# CPU_EBI1_FPGA_Memory.net
KiCad netlist of a schematic drawn in Altium Designer
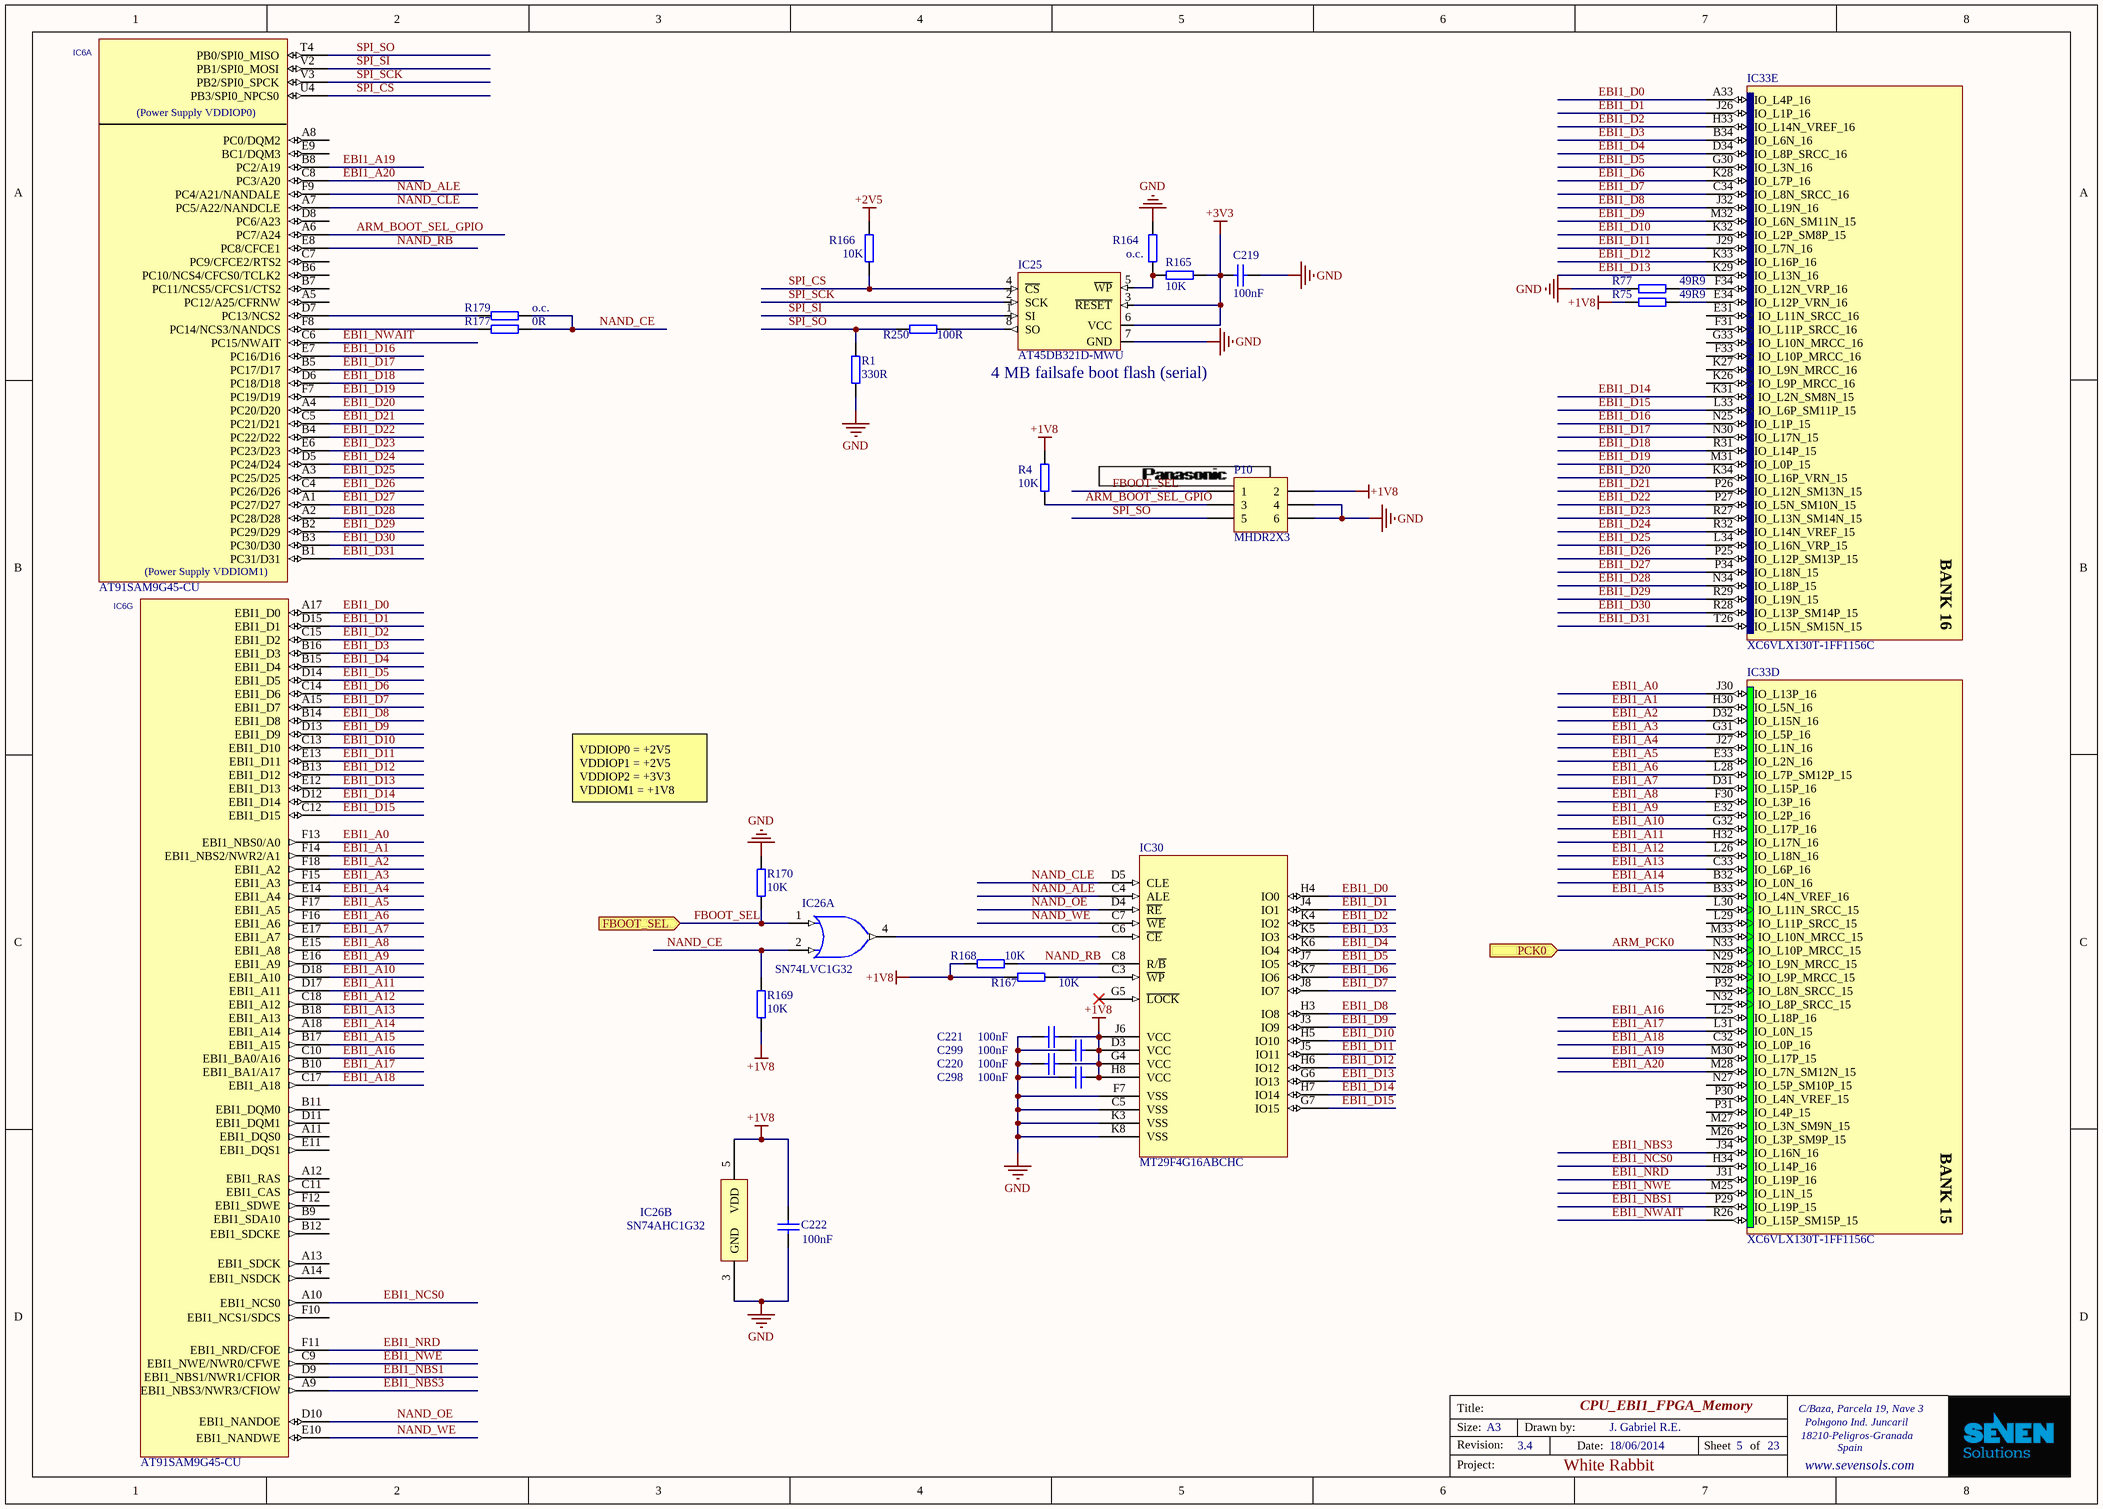
[diagram p0: CPU_EBI1_FPGA_Memory.SchDoc]

(export (version "E")
  (design (tool "Eeschema 10.0.6"))
  (components
    (comp (ref "C219")
      (value "100nF")
      (footprint "CC1005-0402")
      (description "Capacitor")
      (fields
        (field (name "TOLERANCE") "±10%")
        (field (name "VOLTAGE") "16V")
        (field (name "PUBLISHER") "Altium Limited")
      )
      (libsource (lib "wr_switch") (part "Cap"))
    )
    (comp (ref "C220")
      (value "100nF")
      (footprint "CC1005-0402")
      (description "Capacitor")
      (fields
        (field (name "TOLERANCE") "±10%")
        (field (name "VOLTAGE") "16V")
        (field (name "PUBLISHER") "Altium Limited")
      )
      (libsource (lib "wr_switch") (part "Cap"))
    )
    (comp (ref "C221")
      (value "100nF")
      (footprint "CC1005-0402")
      (description "Capacitor")
      (fields
        (field (name "TOLERANCE") "±10%")
        (field (name "VOLTAGE") "16V")
        (field (name "PUBLISHER") "Altium Limited")
      )
      (libsource (lib "wr_switch") (part "Cap"))
    )
    (comp (ref "C222")
      (value "100nF")
      (footprint "CC1005-0402")
      (description "Capacitor")
      (fields
        (field (name "TOLERANCE") "±10%")
        (field (name "VOLTAGE") "16V")
        (field (name "PUBLISHER") "Altium Limited")
      )
      (libsource (lib "wr_switch") (part "Cap"))
    )
    (comp (ref "C298")
      (value "100nF")
      (footprint "CC1005-0402")
      (description "Capacitor")
      (fields
        (field (name "TOLERANCE") "±10%")
        (field (name "VOLTAGE") "16V")
        (field (name "PUBLISHER") "Altium Limited")
      )
      (libsource (lib "wr_switch") (part "Cap"))
    )
    (comp (ref "C299")
      (value "100nF")
      (footprint "CC1005-0402")
      (description "Capacitor")
      (fields
        (field (name "TOLERANCE") "±10%")
        (field (name "VOLTAGE") "16V")
        (field (name "PUBLISHER") "Altium Limited")
      )
      (libsource (lib "wr_switch") (part "Cap"))
    )
    (comp (ref "IC6")
      (value "AT91SAM9G45-CU")
      (footprint "TFBGA324")
      (description "Atmel 400MHz ARM926 MCU")
      (libsource (lib "wr_switch") (part "AT91SAM9G45-CU"))
    )
    (comp (ref "IC25")
      (value "AT45DB321D-MWU")
      (footprint "7S_WR:8MW_8CN3_Merge")
      (description "64-megabit 2.7V, Dual-Interface DataFlash")
      (libsource (lib "wr_switch") (part "AT45DB642D"))
    )
    (comp (ref "IC26")
      (value "SN74LVC1G32")
      (footprint "SOT23-5AL")
      (description "TI single OR gate")
      (libsource (lib "wr_switch") (part "SN74AHC1G32"))
    )
    (comp (ref "IC30")
      (value "MT29F4G16ABCHC")
      (footprint "7S_WR:VFBGA63")
      (description "NAND Flash 256Mx16, 1.8V Asynch/Page")
      (libsource (lib "wr_switch") (part "MT29F4G16ABCHC"))
    )
    (comp (ref "IC33")
      (value "XC6VLX130T-1FF1156C")
      (footprint "FF1156")
      (fields (field (name "PUBLISHER") "Altium Limited"))
      (libsource (lib "Xilinx Virtex-6") (part "XC6VLX130T-1FF1156C"))
    )
    (comp (ref "P10")
      (value "MHDR2X3")
      (footprint "7S_WR:MHDR2X3_1.27mm")
      (description "SMD Header, 3-Pin, Dual row, 2.54mm pitch")
      (libsource (lib "Miscellaneous Connectors") (part "MHDR2X3"))
    )
    (comp (ref "R1")
      (value "330R")
      (footprint "0402")
      (description "SMD Resistor")
      (fields (field (name "TOLERANCE") "±1%"))
      (libsource (lib "wr_switch") (part "RES_SMD"))
    )
    (comp (ref "R4")
      (value "10K")
      (footprint "0402")
      (description "SMD Resistor")
      (fields (field (name "TOLERANCE") "±1%"))
      (libsource (lib "wr_switch") (part "RES_SMD"))
    )
    (comp (ref "R75")
      (value "49R9")
      (footprint "0402")
      (description "SMD Resistor")
      (fields (field (name "TOLERANCE") "±1%"))
      (libsource (lib "wr_switch") (part "RES_SMD"))
    )
    (comp (ref "R77")
      (value "49R9")
      (footprint "0402")
      (description "SMD Resistor")
      (fields (field (name "TOLERANCE") "±1%"))
      (libsource (lib "wr_switch") (part "RES_SMD"))
    )
    (comp (ref "R164")
      (value "o.c.")
      (footprint "0402")
      (description "SMD Resistor")
      (libsource (lib "wr_switch") (part "RES_SMD"))
    )
    (comp (ref "R165")
      (value "10K")
      (footprint "0402")
      (description "SMD Resistor")
      (fields (field (name "TOLERANCE") "±1%"))
      (libsource (lib "wr_switch") (part "RES_SMD"))
    )
    (comp (ref "R166")
      (value "10K")
      (footprint "0402")
      (description "SMD Resistor")
      (fields (field (name "TOLERANCE") "±1%"))
      (libsource (lib "wr_switch") (part "RES_SMD"))
    )
    (comp (ref "R167")
      (value "10K")
      (footprint "0402")
      (description "SMD Resistor")
      (fields (field (name "TOLERANCE") "±1%"))
      (libsource (lib "wr_switch") (part "RES_SMD"))
    )
    (comp (ref "R168")
      (value "10K")
      (footprint "0402")
      (description "SMD Resistor")
      (fields (field (name "TOLERANCE") "±1%"))
      (libsource (lib "wr_switch") (part "RES_SMD"))
    )
    (comp (ref "R169")
      (value "10K")
      (footprint "0402")
      (description "SMD Resistor")
      (fields (field (name "TOLERANCE") "±1%"))
      (libsource (lib "wr_switch") (part "RES_SMD"))
    )
    (comp (ref "R170")
      (value "10K")
      (footprint "0402")
      (description "SMD Resistor")
      (fields (field (name "TOLERANCE") "±1%"))
      (libsource (lib "wr_switch") (part "RES_SMD"))
    )
    (comp (ref "R177")
      (value "0R")
      (footprint "0603")
      (description "SMD Resistor")
      (libsource (lib "wr_switch") (part "RES_SMD"))
    )
    (comp (ref "R179")
      (value "o.c.")
      (footprint "0402")
      (description "SMD Resistor")
      (libsource (lib "wr_switch") (part "RES_SMD"))
    )
    (comp (ref "R250")
      (value "100R")
      (footprint "0402")
      (description "SMD Resistor")
      (fields (field (name "TOLERANCE") "±1%"))
      (libsource (lib "wr_switch") (part "RES_SMD"))
    )
  )
  (nets
    (net (code "1") (name "+1V8") (class "Default")
      (node (ref "C220") (pin "1") (pinfunction "1_1") (pintype "passive"))
      (node (ref "C221") (pin "1") (pinfunction "1_1") (pintype "passive"))
      (node (ref "C222") (pin "2") (pinfunction "2_2") (pintype "passive"))
      (node (ref "C298") (pin "1") (pinfunction "1_1") (pintype "passive"))
      (node (ref "C299") (pin "1") (pinfunction "1_1") (pintype "passive"))
      (node (ref "IC26") (pin "5") (pinfunction "VDD_5") (pintype "passive"))
      (node (ref "IC30") (pin "D3") (pinfunction "VCC_D3") (pintype "power_in"))
      (node (ref "IC30") (pin "G4") (pinfunction "VCC_G4") (pintype "power_in"))
      (node (ref "IC30") (pin "H8") (pinfunction "VCC_H8") (pintype "power_in"))
      (node (ref "IC30") (pin "J6") (pinfunction "VCC_J6") (pintype "power_in"))
      (node (ref "P10") (pin "2") (pinfunction "2_2") (pintype "passive"))
      (node (ref "R167") (pin "2") (pinfunction "2_2") (pintype "passive"))
      (node (ref "R168") (pin "2") (pinfunction "2_2") (pintype "passive"))
      (node (ref "R169") (pin "2") (pinfunction "2_2") (pintype "passive"))
      (node (ref "R4") (pin "2") (pinfunction "2_2") (pintype "passive"))
      (node (ref "R75") (pin "2") (pinfunction "2_2") (pintype "passive"))
    )
    (net (code "2") (name "+2V5") (class "Default")
      (node (ref "R166") (pin "2") (pinfunction "2_2") (pintype "passive"))
    )
    (net (code "3") (name "+3V3") (class "Default")
      (node (ref "C219") (pin "1") (pinfunction "1_1") (pintype "passive"))
      (node (ref "IC25") (pin "3") (pinfunction "~{RESET}_3") (pintype "input"))
      (node (ref "IC25") (pin "6") (pinfunction "VCC_6") (pintype "power_in"))
      (node (ref "R165") (pin "2") (pinfunction "2_2") (pintype "passive"))
    )
    (net (code "4") (name "/ARM_BOOT_SEL_GPIO") (class "Default")
      (node (ref "IC6") (pin "A6") (pinfunction "PC7/A24_A6") (pintype "bidirectional"))
      (node (ref "P10") (pin "3") (pinfunction "3_3") (pintype "passive"))
      (node (ref "R4") (pin "1") (pinfunction "1_1") (pintype "passive"))
    )
    (net (code "5") (name "/ARM_PCK0") (class "Default")
      (node (ref "IC33") (pin "N33") (pinfunction "IO_L10P_MRCC_15_N33") (pintype "bidirectional"))
    )
    (net (code "6") (name "/EBI1_A0") (class "Default")
      (node (ref "IC33") (pin "J30") (pinfunction "IO_L13P_16_J30") (pintype "bidirectional"))
      (node (ref "IC6") (pin "F13") (pinfunction "EBI1_NBS0/A0_F13") (pintype "output"))
    )
    (net (code "7") (name "/EBI1_A1") (class "Default")
      (node (ref "IC33") (pin "H30") (pinfunction "IO_L5N_16_H30") (pintype "bidirectional"))
      (node (ref "IC6") (pin "F14") (pinfunction "EBI1_NBS2/NWR2/A1_F14") (pintype "output"))
    )
    (net (code "8") (name "/EBI1_A2") (class "Default")
      (node (ref "IC33") (pin "D32") (pinfunction "IO_L15N_16_D32") (pintype "bidirectional"))
      (node (ref "IC6") (pin "F18") (pinfunction "EBI1_A2_F18") (pintype "output"))
    )
    (net (code "9") (name "/EBI1_A3") (class "Default")
      (node (ref "IC33") (pin "G31") (pinfunction "IO_L5P_16_G31") (pintype "bidirectional"))
      (node (ref "IC6") (pin "F15") (pinfunction "EBI1_A3_F15") (pintype "output"))
    )
    (net (code "10") (name "/EBI1_A4") (class "Default")
      (node (ref "IC33") (pin "J27") (pinfunction "IO_L1N_16_J27") (pintype "bidirectional"))
      (node (ref "IC6") (pin "E14") (pinfunction "EBI1_A4_E14") (pintype "output"))
    )
    (net (code "11") (name "/EBI1_A5") (class "Default")
      (node (ref "IC33") (pin "E33") (pinfunction "IO_L2N_16_E33") (pintype "bidirectional"))
      (node (ref "IC6") (pin "F17") (pinfunction "EBI1_A5_F17") (pintype "output"))
    )
    (net (code "12") (name "/EBI1_A6") (class "Default")
      (node (ref "IC33") (pin "L28") (pinfunction "IO_L7P_SM12P_15_L28") (pintype "bidirectional"))
      (node (ref "IC6") (pin "F16") (pinfunction "EBI1_A6_F16") (pintype "output"))
    )
    (net (code "13") (name "/EBI1_A7") (class "Default")
      (node (ref "IC33") (pin "D31") (pinfunction "IO_L15P_16_D31") (pintype "bidirectional"))
      (node (ref "IC6") (pin "E17") (pinfunction "EBI1_A7_E17") (pintype "output"))
    )
    (net (code "14") (name "/EBI1_A8") (class "Default")
      (node (ref "IC33") (pin "F30") (pinfunction "IO_L3P_16_F30") (pintype "bidirectional"))
      (node (ref "IC6") (pin "E15") (pinfunction "EBI1_A8_E15") (pintype "output"))
    )
    (net (code "15") (name "/EBI1_A9") (class "Default")
      (node (ref "IC33") (pin "E32") (pinfunction "IO_L2P_16_E32") (pintype "bidirectional"))
      (node (ref "IC6") (pin "E16") (pinfunction "EBI1_A9_E16") (pintype "output"))
    )
    (net (code "16") (name "/EBI1_A10") (class "Default")
      (node (ref "IC33") (pin "G32") (pinfunction "IO_L17P_16_G32") (pintype "bidirectional"))
      (node (ref "IC6") (pin "D18") (pinfunction "EBI1_A10_D18") (pintype "output"))
    )
    (net (code "17") (name "/EBI1_A11") (class "Default")
      (node (ref "IC33") (pin "H32") (pinfunction "IO_L17N_16_H32") (pintype "bidirectional"))
      (node (ref "IC6") (pin "D17") (pinfunction "EBI1_A11_D17") (pintype "output"))
    )
    (net (code "18") (name "/EBI1_A12") (class "Default")
      (node (ref "IC33") (pin "L26") (pinfunction "IO_L18N_16_L26") (pintype "bidirectional"))
      (node (ref "IC6") (pin "C18") (pinfunction "EBI1_A12_C18") (pintype "output"))
    )
    (net (code "19") (name "/EBI1_A13") (class "Default")
      (node (ref "IC33") (pin "C33") (pinfunction "IO_L6P_16_C33") (pintype "bidirectional"))
      (node (ref "IC6") (pin "B18") (pinfunction "EBI1_A13_B18") (pintype "output"))
    )
    (net (code "20") (name "/EBI1_A14") (class "Default")
      (node (ref "IC33") (pin "B32") (pinfunction "IO_L0N_16_B32") (pintype "bidirectional"))
      (node (ref "IC6") (pin "A18") (pinfunction "EBI1_A14_A18") (pintype "output"))
    )
    (net (code "21") (name "/EBI1_A15") (class "Default")
      (node (ref "IC33") (pin "B33") (pinfunction "IO_L4N_VREF_16_B33") (pintype "bidirectional"))
      (node (ref "IC6") (pin "B17") (pinfunction "EBI1_A15_B17") (pintype "output"))
    )
    (net (code "22") (name "/EBI1_A16") (class "Default")
      (node (ref "IC33") (pin "L25") (pinfunction "IO_L18P_16_L25") (pintype "bidirectional"))
      (node (ref "IC6") (pin "C10") (pinfunction "EBI1_BA0/A16_C10") (pintype "output"))
    )
    (net (code "23") (name "/EBI1_A17") (class "Default")
      (node (ref "IC33") (pin "L31") (pinfunction "IO_L0N_15_L31") (pintype "bidirectional"))
      (node (ref "IC6") (pin "B10") (pinfunction "EBI1_BA1/A17_B10") (pintype "output"))
    )
    (net (code "24") (name "/EBI1_A18") (class "Default")
      (node (ref "IC33") (pin "C32") (pinfunction "IO_L0P_16_C32") (pintype "bidirectional"))
      (node (ref "IC6") (pin "C17") (pinfunction "EBI1_A18_C17") (pintype "output"))
    )
    (net (code "25") (name "/EBI1_A19") (class "Default")
      (node (ref "IC33") (pin "M30") (pinfunction "IO_L17P_15_M30") (pintype "bidirectional"))
      (node (ref "IC6") (pin "B8") (pinfunction "PC2/A19_B8") (pintype "bidirectional"))
    )
    (net (code "26") (name "/EBI1_A20") (class "Default")
      (node (ref "IC33") (pin "M28") (pinfunction "IO_L7N_SM12N_15_M28") (pintype "bidirectional"))
      (node (ref "IC6") (pin "C8") (pinfunction "PC3/A20_C8") (pintype "bidirectional"))
    )
    (net (code "27") (name "/EBI1_D0") (class "Default")
      (node (ref "IC30") (pin "H4") (pinfunction "IO0_H4") (pintype "bidirectional"))
      (node (ref "IC33") (pin "A33") (pinfunction "IO_L4P_16_A33") (pintype "bidirectional"))
      (node (ref "IC6") (pin "A17") (pinfunction "EBI1_D0_A17") (pintype "bidirectional"))
    )
    (net (code "28") (name "/EBI1_D1") (class "Default")
      (node (ref "IC30") (pin "J4") (pinfunction "IO1_J4") (pintype "bidirectional"))
      (node (ref "IC33") (pin "J26") (pinfunction "IO_L1P_16_J26") (pintype "bidirectional"))
      (node (ref "IC6") (pin "D15") (pinfunction "EBI1_D1_D15") (pintype "bidirectional"))
    )
    (net (code "29") (name "/EBI1_D2") (class "Default")
      (node (ref "IC30") (pin "K4") (pinfunction "IO2_K4") (pintype "bidirectional"))
      (node (ref "IC33") (pin "H33") (pinfunction "IO_L14N_VREF_16_H33") (pintype "bidirectional"))
      (node (ref "IC6") (pin "C15") (pinfunction "EBI1_D2_C15") (pintype "bidirectional"))
    )
    (net (code "30") (name "/EBI1_D3") (class "Default")
      (node (ref "IC30") (pin "K5") (pinfunction "IO3_K5") (pintype "bidirectional"))
      (node (ref "IC33") (pin "B34") (pinfunction "IO_L6N_16_B34") (pintype "bidirectional"))
      (node (ref "IC6") (pin "B16") (pinfunction "EBI1_D3_B16") (pintype "bidirectional"))
    )
    (net (code "31") (name "/EBI1_D4") (class "Default")
      (node (ref "IC30") (pin "K6") (pinfunction "IO4_K6") (pintype "bidirectional"))
      (node (ref "IC33") (pin "D34") (pinfunction "IO_L8P_SRCC_16_D34") (pintype "bidirectional"))
      (node (ref "IC6") (pin "B15") (pinfunction "EBI1_D4_B15") (pintype "bidirectional"))
    )
    (net (code "32") (name "/EBI1_D5") (class "Default")
      (node (ref "IC30") (pin "J7") (pinfunction "IO5_J7") (pintype "bidirectional"))
      (node (ref "IC33") (pin "G30") (pinfunction "IO_L3N_16_G30") (pintype "bidirectional"))
      (node (ref "IC6") (pin "D14") (pinfunction "EBI1_D5_D14") (pintype "bidirectional"))
    )
    (net (code "33") (name "/EBI1_D6") (class "Default")
      (node (ref "IC30") (pin "K7") (pinfunction "IO6_K7") (pintype "bidirectional"))
      (node (ref "IC33") (pin "K28") (pinfunction "IO_L7P_16_K28") (pintype "bidirectional"))
      (node (ref "IC6") (pin "C14") (pinfunction "EBI1_D6_C14") (pintype "bidirectional"))
    )
    (net (code "34") (name "/EBI1_D7") (class "Default")
      (node (ref "IC30") (pin "J8") (pinfunction "IO7_J8") (pintype "bidirectional"))
      (node (ref "IC33") (pin "C34") (pinfunction "IO_L8N_SRCC_16_C34") (pintype "bidirectional"))
      (node (ref "IC6") (pin "A15") (pinfunction "EBI1_D7_A15") (pintype "bidirectional"))
    )
    (net (code "35") (name "/EBI1_D8") (class "Default")
      (node (ref "IC30") (pin "H3") (pinfunction "IO8_H3") (pintype "bidirectional"))
      (node (ref "IC33") (pin "J32") (pinfunction "IO_L19N_16_J32") (pintype "bidirectional"))
      (node (ref "IC6") (pin "B14") (pinfunction "EBI1_D8_B14") (pintype "bidirectional"))
    )
    (net (code "36") (name "/EBI1_D9") (class "Default")
      (node (ref "IC30") (pin "J3") (pinfunction "IO9_J3") (pintype "bidirectional"))
      (node (ref "IC33") (pin "M32") (pinfunction "IO_L6N_SM11N_15_M32") (pintype "bidirectional"))
      (node (ref "IC6") (pin "D13") (pinfunction "EBI1_D9_D13") (pintype "bidirectional"))
    )
    (net (code "37") (name "/EBI1_D10") (class "Default")
      (node (ref "IC30") (pin "H5") (pinfunction "IO10_H5") (pintype "bidirectional"))
      (node (ref "IC33") (pin "K32") (pinfunction "IO_L2P_SM8P_15_K32") (pintype "bidirectional"))
      (node (ref "IC6") (pin "C13") (pinfunction "EBI1_D10_C13") (pintype "bidirectional"))
    )
    (net (code "38") (name "/EBI1_D11") (class "Default")
      (node (ref "IC30") (pin "J5") (pinfunction "IO11_J5") (pintype "bidirectional"))
      (node (ref "IC33") (pin "J29") (pinfunction "IO_L7N_16_J29") (pintype "bidirectional"))
      (node (ref "IC6") (pin "E13") (pinfunction "EBI1_D11_E13") (pintype "bidirectional"))
    )
    (net (code "39") (name "/EBI1_D12") (class "Default")
      (node (ref "IC30") (pin "H6") (pinfunction "IO12_H6") (pintype "bidirectional"))
      (node (ref "IC33") (pin "K33") (pinfunction "IO_L16P_16_K33") (pintype "bidirectional"))
      (node (ref "IC6") (pin "B13") (pinfunction "EBI1_D12_B13") (pintype "bidirectional"))
    )
    (net (code "40") (name "/EBI1_D13") (class "Default")
      (node (ref "IC30") (pin "G6") (pinfunction "IO13_G6") (pintype "bidirectional"))
      (node (ref "IC33") (pin "K29") (pinfunction "IO_L13N_16_K29") (pintype "bidirectional"))
      (node (ref "IC6") (pin "E12") (pinfunction "EBI1_D13_E12") (pintype "bidirectional"))
    )
    (net (code "41") (name "/EBI1_D14") (class "Default")
      (node (ref "IC30") (pin "H7") (pinfunction "IO14_H7") (pintype "bidirectional"))
      (node (ref "IC33") (pin "K31") (pinfunction "IO_L2N_SM8N_15_K31") (pintype "bidirectional"))
      (node (ref "IC6") (pin "D12") (pinfunction "EBI1_D14_D12") (pintype "bidirectional"))
    )
    (net (code "42") (name "/EBI1_D15") (class "Default")
      (node (ref "IC30") (pin "G7") (pinfunction "IO15_G7") (pintype "bidirectional"))
      (node (ref "IC33") (pin "L33") (pinfunction "IO_L6P_SM11P_15_L33") (pintype "bidirectional"))
      (node (ref "IC6") (pin "C12") (pinfunction "EBI1_D15_C12") (pintype "bidirectional"))
    )
    (net (code "43") (name "/EBI1_D16") (class "Default")
      (node (ref "IC33") (pin "N25") (pinfunction "IO_L1P_15_N25") (pintype "bidirectional"))
      (node (ref "IC6") (pin "E7") (pinfunction "PC16/D16_E7") (pintype "bidirectional"))
    )
    (net (code "44") (name "/EBI1_D17") (class "Default")
      (node (ref "IC33") (pin "N30") (pinfunction "IO_L17N_15_N30") (pintype "bidirectional"))
      (node (ref "IC6") (pin "B5") (pinfunction "PC17/D17_B5") (pintype "bidirectional"))
    )
    (net (code "45") (name "/EBI1_D18") (class "Default")
      (node (ref "IC33") (pin "R31") (pinfunction "IO_L14P_15_R31") (pintype "bidirectional"))
      (node (ref "IC6") (pin "D6") (pinfunction "PC18/D18_D6") (pintype "bidirectional"))
    )
    (net (code "46") (name "/EBI1_D19") (class "Default")
      (node (ref "IC33") (pin "M31") (pinfunction "IO_L0P_15_M31") (pintype "bidirectional"))
      (node (ref "IC6") (pin "F7") (pinfunction "PC19/D19_F7") (pintype "bidirectional"))
    )
    (net (code "47") (name "/EBI1_D20") (class "Default")
      (node (ref "IC33") (pin "K34") (pinfunction "IO_L16P_VRN_15_K34") (pintype "bidirectional"))
      (node (ref "IC6") (pin "A4") (pinfunction "PC20/D20_A4") (pintype "bidirectional"))
    )
    (net (code "48") (name "/EBI1_D21") (class "Default")
      (node (ref "IC33") (pin "P26") (pinfunction "IO_L12N_SM13N_15_P26") (pintype "bidirectional"))
      (node (ref "IC6") (pin "C5") (pinfunction "PC21/D21_C5") (pintype "bidirectional"))
    )
    (net (code "49") (name "/EBI1_D22") (class "Default")
      (node (ref "IC33") (pin "P27") (pinfunction "IO_L5N_SM10N_15_P27") (pintype "bidirectional"))
      (node (ref "IC6") (pin "B4") (pinfunction "PC22/D22_B4") (pintype "bidirectional"))
    )
    (net (code "50") (name "/EBI1_D23") (class "Default")
      (node (ref "IC33") (pin "R27") (pinfunction "IO_L13N_SM14N_15_R27") (pintype "bidirectional"))
      (node (ref "IC6") (pin "E6") (pinfunction "PC23/D23_E6") (pintype "bidirectional"))
    )
    (net (code "51") (name "/EBI1_D24") (class "Default")
      (node (ref "IC33") (pin "R32") (pinfunction "IO_L14N_VREF_15_R32") (pintype "bidirectional"))
      (node (ref "IC6") (pin "D5") (pinfunction "PC24/D24_D5") (pintype "bidirectional"))
    )
    (net (code "52") (name "/EBI1_D25") (class "Default")
      (node (ref "IC33") (pin "L34") (pinfunction "IO_L16N_VRP_15_L34") (pintype "bidirectional"))
      (node (ref "IC6") (pin "A3") (pinfunction "PC25/D25_A3") (pintype "bidirectional"))
    )
    (net (code "53") (name "/EBI1_D26") (class "Default")
      (node (ref "IC33") (pin "P25") (pinfunction "IO_L12P_SM13P_15_P25") (pintype "bidirectional"))
      (node (ref "IC6") (pin "C4") (pinfunction "PC26/D26_C4") (pintype "bidirectional"))
    )
    (net (code "54") (name "/EBI1_D27") (class "Default")
      (node (ref "IC33") (pin "P34") (pinfunction "IO_L18N_15_P34") (pintype "bidirectional"))
      (node (ref "IC6") (pin "A1") (pinfunction "PC27/D27_A1") (pintype "bidirectional"))
    )
    (net (code "55") (name "/EBI1_D28") (class "Default")
      (node (ref "IC33") (pin "N34") (pinfunction "IO_L18P_15_N34") (pintype "bidirectional"))
      (node (ref "IC6") (pin "A2") (pinfunction "PC28/D28_A2") (pintype "bidirectional"))
    )
    (net (code "56") (name "/EBI1_D29") (class "Default")
      (node (ref "IC33") (pin "R29") (pinfunction "IO_L19N_15_R29") (pintype "bidirectional"))
      (node (ref "IC6") (pin "B2") (pinfunction "PC29/D29_B2") (pintype "bidirectional"))
    )
    (net (code "57") (name "/EBI1_D30") (class "Default")
      (node (ref "IC33") (pin "R28") (pinfunction "IO_L13P_SM14P_15_R28") (pintype "bidirectional"))
      (node (ref "IC6") (pin "B3") (pinfunction "PC30/D30_B3") (pintype "bidirectional"))
    )
    (net (code "58") (name "/EBI1_D31") (class "Default")
      (node (ref "IC33") (pin "T26") (pinfunction "IO_L15N_SM15N_15_T26") (pintype "bidirectional"))
      (node (ref "IC6") (pin "B1") (pinfunction "PC31/D31_B1") (pintype "bidirectional"))
    )
    (net (code "59") (name "/EBI1_NBS1") (class "Default")
      (node (ref "IC33") (pin "P29") (pinfunction "IO_L19P_15_P29") (pintype "bidirectional"))
      (node (ref "IC6") (pin "D9") (pinfunction "EBI1_NBS1/NWR1/CFIOR_D9") (pintype "output"))
    )
    (net (code "60") (name "/EBI1_NBS3") (class "Default")
      (node (ref "IC33") (pin "J34") (pinfunction "IO_L16N_16_J34") (pintype "bidirectional"))
      (node (ref "IC6") (pin "A9") (pinfunction "EBI1_NBS3/NWR3/CFIOW_A9") (pintype "output"))
    )
    (net (code "61") (name "/EBI1_NCS0") (class "Default")
      (node (ref "IC33") (pin "H34") (pinfunction "IO_L14P_16_H34") (pintype "bidirectional"))
      (node (ref "IC6") (pin "A10") (pinfunction "EBI1_NCS0_A10") (pintype "output"))
    )
    (net (code "62") (name "/EBI1_NRD") (class "Default")
      (node (ref "IC33") (pin "J31") (pinfunction "IO_L19P_16_J31") (pintype "bidirectional"))
      (node (ref "IC6") (pin "F11") (pinfunction "EBI1_NRD/CFOE_F11") (pintype "output"))
    )
    (net (code "63") (name "/EBI1_NWAIT") (class "Default")
      (node (ref "IC33") (pin "R26") (pinfunction "IO_L15P_SM15P_15_R26") (pintype "bidirectional"))
      (node (ref "IC6") (pin "C6") (pinfunction "PC15/NWAIT_C6") (pintype "bidirectional"))
    )
    (net (code "64") (name "/EBI1_NWE") (class "Default")
      (node (ref "IC33") (pin "M25") (pinfunction "IO_L1N_15_M25") (pintype "bidirectional"))
      (node (ref "IC6") (pin "C9") (pinfunction "EBI1_NWE/NWR0/CFWE_C9") (pintype "output"))
    )
    (net (code "65") (name "/FBOOT_SEL") (class "Default")
      (node (ref "IC26") (pin "1") (pinfunction "A_1") (pintype "input"))
      (node (ref "P10") (pin "1") (pinfunction "1_1") (pintype "passive"))
      (node (ref "R170") (pin "1") (pinfunction "1_1") (pintype "passive"))
    )
    (net (code "66") (name "/NAND_ALE") (class "Default")
      (node (ref "IC30") (pin "C4") (pinfunction "ALE_C4") (pintype "input"))
      (node (ref "IC6") (pin "F9") (pinfunction "PC4/A21/NANDALE_F9") (pintype "bidirectional"))
    )
    (net (code "67") (name "/NAND_CE") (class "Default")
      (node (ref "IC26") (pin "2") (pinfunction "B_2") (pintype "input"))
      (node (ref "R169") (pin "1") (pinfunction "1_1") (pintype "passive"))
      (node (ref "R177") (pin "1") (pinfunction "1_1") (pintype "passive"))
      (node (ref "R179") (pin "1") (pinfunction "1_1") (pintype "passive"))
    )
    (net (code "68") (name "/NAND_CLE") (class "Default")
      (node (ref "IC30") (pin "D5") (pinfunction "CLE_D5") (pintype "input"))
      (node (ref "IC6") (pin "A7") (pinfunction "PC5/A22/NANDCLE_A7") (pintype "bidirectional"))
    )
    (net (code "69") (name "/NAND_OE") (class "Default")
      (node (ref "IC30") (pin "D4") (pinfunction "~{RE}_D4") (pintype "input"))
      (node (ref "IC6") (pin "D10") (pinfunction "EBI1_NANDOE_D10") (pintype "bidirectional"))
    )
    (net (code "70") (name "/NAND_RB") (class "Default")
      (node (ref "IC30") (pin "C8") (pinfunction "R/~{B}_C8") (pintype "open_collector"))
      (node (ref "IC6") (pin "E8") (pinfunction "PC8/CFCE1_E8") (pintype "bidirectional"))
      (node (ref "R168") (pin "1") (pinfunction "1_1") (pintype "passive"))
    )
    (net (code "71") (name "/NAND_WE") (class "Default")
      (node (ref "IC30") (pin "C7") (pinfunction "~{WE}_C7") (pintype "input"))
      (node (ref "IC6") (pin "E10") (pinfunction "EBI1_NANDWE_E10") (pintype "bidirectional"))
    )
    (net (code "72") (name "/SPI_CS") (class "Default")
      (node (ref "IC25") (pin "4") (pinfunction "~{CS}_4") (pintype "input"))
      (node (ref "IC6") (pin "U4") (pinfunction "PB3/SPI0_NPCS0_U4") (pintype "bidirectional"))
      (node (ref "R166") (pin "1") (pinfunction "1_1") (pintype "passive"))
    )
    (net (code "73") (name "/SPI_SCK") (class "Default")
      (node (ref "IC25") (pin "2") (pinfunction "SCK_2") (pintype "input"))
      (node (ref "IC6") (pin "V3") (pinfunction "PB2/SPI0_SPCK_V3") (pintype "bidirectional"))
    )
    (net (code "74") (name "/SPI_SI") (class "Default")
      (node (ref "IC25") (pin "1") (pinfunction "SI_1") (pintype "input"))
      (node (ref "IC6") (pin "V2") (pinfunction "PB1/SPI0_MOSI_V2") (pintype "bidirectional"))
    )
    (net (code "75") (name "/SPI_SO") (class "Default")
      (node (ref "IC6") (pin "T4") (pinfunction "PB0/SPI0_MISO_T4") (pintype "bidirectional"))
      (node (ref "P10") (pin "5") (pinfunction "5_5") (pintype "passive"))
      (node (ref "R1") (pin "2") (pinfunction "2_2") (pintype "passive"))
      (node (ref "R250") (pin "2") (pinfunction "2_2") (pintype "passive"))
    )
    (net (code "76") (name "GND") (class "Default")
      (node (ref "C219") (pin "2") (pinfunction "2_2") (pintype "passive"))
      (node (ref "C220") (pin "2") (pinfunction "2_2") (pintype "passive"))
      (node (ref "C221") (pin "2") (pinfunction "2_2") (pintype "passive"))
      (node (ref "C222") (pin "1") (pinfunction "1_1") (pintype "passive"))
      (node (ref "C298") (pin "2") (pinfunction "2_2") (pintype "passive"))
      (node (ref "C299") (pin "2") (pinfunction "2_2") (pintype "passive"))
      (node (ref "IC25") (pin "7") (pinfunction "GND_7") (pintype "power_in"))
      (node (ref "IC26") (pin "3") (pinfunction "GND_3") (pintype "passive"))
      (node (ref "IC30") (pin "C5") (pinfunction "VSS_C5") (pintype "power_in"))
      (node (ref "IC30") (pin "F7") (pinfunction "VSS_F7") (pintype "power_in"))
      (node (ref "IC30") (pin "K3") (pinfunction "VSS_K3") (pintype "power_in"))
      (node (ref "IC30") (pin "K8") (pinfunction "VSS_K8") (pintype "power_in"))
      (node (ref "P10") (pin "4") (pinfunction "4_4") (pintype "passive"))
      (node (ref "P10") (pin "6") (pinfunction "6_6") (pintype "passive"))
      (node (ref "R1") (pin "1") (pinfunction "1_1") (pintype "passive"))
      (node (ref "R164") (pin "1") (pinfunction "1_1") (pintype "passive"))
      (node (ref "R170") (pin "2") (pinfunction "2_2") (pintype "passive"))
      (node (ref "R77") (pin "2") (pinfunction "2_2") (pintype "passive"))
    )
    (net (code "77") (name "Net-(IC6A-PC13{slash}NCS2)") (class "Default")
      (node (ref "IC6") (pin "D7") (pinfunction "PC13/NCS2_D7") (pintype "bidirectional"))
      (node (ref "R179") (pin "2") (pinfunction "2_2") (pintype "passive"))
    )
    (net (code "78") (name "Net-(IC6A-PC14{slash}NCS3{slash}NANDCS)") (class "Default")
      (node (ref "IC6") (pin "F8") (pinfunction "PC14/NCS3/NANDCS_F8") (pintype "bidirectional"))
      (node (ref "R177") (pin "2") (pinfunction "2_2") (pintype "passive"))
    )
    (net (code "79") (name "Net-(IC25-SO)") (class "Default")
      (node (ref "IC25") (pin "8") (pinfunction "SO_8") (pintype "output"))
      (node (ref "R250") (pin "1") (pinfunction "1_1") (pintype "passive"))
    )
    (net (code "80") (name "Net-(IC25-~{WP})") (class "Default")
      (node (ref "IC25") (pin "5") (pinfunction "~{WP}_5") (pintype "input"))
      (node (ref "R164") (pin "2") (pinfunction "2_2") (pintype "passive"))
      (node (ref "R165") (pin "1") (pinfunction "1_1") (pintype "passive"))
    )
    (net (code "81") (name "Net-(IC26A-Y)") (class "Default")
      (node (ref "IC26") (pin "4") (pinfunction "Y_4") (pintype "output"))
      (node (ref "IC30") (pin "C6") (pinfunction "~{CE}_C6") (pintype "input"))
    )
    (net (code "82") (name "Net-(IC30-~{WP})") (class "Default")
      (node (ref "IC30") (pin "C3") (pinfunction "~{WP}_C3") (pintype "input"))
      (node (ref "R167") (pin "1") (pinfunction "1_1") (pintype "passive"))
    )
    (net (code "83") (name "Net-(IC33E-IO_L12N_VRP_16)") (class "Default")
      (node (ref "IC33") (pin "F34") (pinfunction "IO_L12N_VRP_16_F34") (pintype "bidirectional"))
      (node (ref "R77") (pin "1") (pinfunction "1_1") (pintype "passive"))
    )
    (net (code "84") (name "Net-(IC33E-IO_L12P_VRN_16)") (class "Default")
      (node (ref "IC33") (pin "E34") (pinfunction "IO_L12P_VRN_16_E34") (pintype "bidirectional"))
      (node (ref "R75") (pin "1") (pinfunction "1_1") (pintype "passive"))
    )
    (net (code "85") (name "unconnected-(IC6A-BC1{slash}DQM3-PadE9)") (class "Default")
      (node (ref "IC6") (pin "E9") (pinfunction "BC1/DQM3_E9") (pintype "bidirectional"))
    )
    (net (code "86") (name "unconnected-(IC6A-PC0{slash}DQM2-PadA8)") (class "Default")
      (node (ref "IC6") (pin "A8") (pinfunction "PC0/DQM2_A8") (pintype "bidirectional"))
    )
    (net (code "87") (name "unconnected-(IC6A-PC6{slash}A23-PadD8)") (class "Default")
      (node (ref "IC6") (pin "D8") (pinfunction "PC6/A23_D8") (pintype "bidirectional"))
    )
    (net (code "88") (name "unconnected-(IC6A-PC9{slash}CFCE2{slash}RTS2-PadC7)") (class "Default")
      (node (ref "IC6") (pin "C7") (pinfunction "PC9/CFCE2/RTS2_C7") (pintype "bidirectional"))
    )
    (net (code "89") (name "unconnected-(IC6A-PC10{slash}NCS4{slash}CFCS0{slash}TCLK2-PadB6)") (class "Default")
      (node (ref "IC6") (pin "B6") (pinfunction "PC10/NCS4/CFCS0/TCLK2_B6") (pintype "bidirectional"))
    )
    (net (code "90") (name "unconnected-(IC6A-PC11{slash}NCS5{slash}CFCS1{slash}CTS2-PadB7)") (class "Default")
      (node (ref "IC6") (pin "B7") (pinfunction "PC11/NCS5/CFCS1/CTS2_B7") (pintype "bidirectional"))
    )
    (net (code "91") (name "unconnected-(IC6A-PC12{slash}A25{slash}CFRNW-PadA5)") (class "Default")
      (node (ref "IC6") (pin "A5") (pinfunction "PC12/A25/CFRNW_A5") (pintype "bidirectional"))
    )
    (net (code "92") (name "unconnected-(IC6G-EBI1_CAS-PadC11)") (class "Default")
      (node (ref "IC6") (pin "C11") (pinfunction "EBI1_CAS_C11") (pintype "output"))
    )
    (net (code "93") (name "unconnected-(IC6G-EBI1_DQM0-PadB11)") (class "Default")
      (node (ref "IC6") (pin "B11") (pinfunction "EBI1_DQM0_B11") (pintype "output"))
    )
    (net (code "94") (name "unconnected-(IC6G-EBI1_DQM1-PadD11)") (class "Default")
      (node (ref "IC6") (pin "D11") (pinfunction "EBI1_DQM1_D11") (pintype "output"))
    )
    (net (code "95") (name "unconnected-(IC6G-EBI1_DQS0-PadA11)") (class "Default")
      (node (ref "IC6") (pin "A11") (pinfunction "EBI1_DQS0_A11") (pintype "output"))
    )
    (net (code "96") (name "unconnected-(IC6G-EBI1_DQS1-PadE11)") (class "Default")
      (node (ref "IC6") (pin "E11") (pinfunction "EBI1_DQS1_E11") (pintype "output"))
    )
    (net (code "97") (name "unconnected-(IC6G-EBI1_NCS1{slash}SDCS-PadF10)") (class "Default")
      (node (ref "IC6") (pin "F10") (pinfunction "EBI1_NCS1/SDCS_F10") (pintype "output"))
    )
    (net (code "98") (name "unconnected-(IC6G-EBI1_NSDCK-PadA14)") (class "Default")
      (node (ref "IC6") (pin "A14") (pinfunction "EBI1_NSDCK_A14") (pintype "output"))
    )
    (net (code "99") (name "unconnected-(IC6G-EBI1_RAS-PadA12)") (class "Default")
      (node (ref "IC6") (pin "A12") (pinfunction "EBI1_RAS_A12") (pintype "output"))
    )
    (net (code "100") (name "unconnected-(IC6G-EBI1_SDA10-PadB9)") (class "Default")
      (node (ref "IC6") (pin "B9") (pinfunction "EBI1_SDA10_B9") (pintype "output"))
    )
    (net (code "101") (name "unconnected-(IC6G-EBI1_SDCK-PadA13)") (class "Default")
      (node (ref "IC6") (pin "A13") (pinfunction "EBI1_SDCK_A13") (pintype "output"))
    )
    (net (code "102") (name "unconnected-(IC6G-EBI1_SDCKE-PadB12)") (class "Default")
      (node (ref "IC6") (pin "B12") (pinfunction "EBI1_SDCKE_B12") (pintype "output"))
    )
    (net (code "103") (name "unconnected-(IC6G-EBI1_SDWE-PadF12)") (class "Default")
      (node (ref "IC6") (pin "F12") (pinfunction "EBI1_SDWE_F12") (pintype "output"))
    )
    (net (code "104") (name "unconnected-(IC30-~{LOCK}-PadG5)") (class "Default")
      (node (ref "IC30") (pin "G5") (pinfunction "~{LOCK}_G5") (pintype "input+no_connect"))
    )
    (net (code "105") (name "unconnected-(IC33D-IO_L3N_SM9N_15-PadM27)") (class "Default")
      (node (ref "IC33") (pin "M27") (pinfunction "IO_L3N_SM9N_15_M27") (pintype "bidirectional"))
    )
    (net (code "106") (name "unconnected-(IC33D-IO_L3P_SM9P_15-PadM26)") (class "Default")
      (node (ref "IC33") (pin "M26") (pinfunction "IO_L3P_SM9P_15_M26") (pintype "bidirectional"))
    )
    (net (code "107") (name "unconnected-(IC33D-IO_L4N_VREF_15-PadP30)") (class "Default")
      (node (ref "IC33") (pin "P30") (pinfunction "IO_L4N_VREF_15_P30") (pintype "bidirectional"))
    )
    (net (code "108") (name "unconnected-(IC33D-IO_L4P_15-PadP31)") (class "Default")
      (node (ref "IC33") (pin "P31") (pinfunction "IO_L4P_15_P31") (pintype "bidirectional"))
    )
    (net (code "109") (name "unconnected-(IC33D-IO_L5P_SM10P_15-PadN27)") (class "Default")
      (node (ref "IC33") (pin "N27") (pinfunction "IO_L5P_SM10P_15_N27") (pintype "bidirectional"))
    )
    (net (code "110") (name "unconnected-(IC33D-IO_L8N_SRCC_15-PadP32)") (class "Default")
      (node (ref "IC33") (pin "P32") (pinfunction "IO_L8N_SRCC_15_P32") (pintype "bidirectional"))
    )
    (net (code "111") (name "unconnected-(IC33D-IO_L8P_SRCC_15-PadN32)") (class "Default")
      (node (ref "IC33") (pin "N32") (pinfunction "IO_L8P_SRCC_15_N32") (pintype "bidirectional"))
    )
    (net (code "112") (name "unconnected-(IC33D-IO_L9N_MRCC_15-PadN29)") (class "Default")
      (node (ref "IC33") (pin "N29") (pinfunction "IO_L9N_MRCC_15_N29") (pintype "bidirectional"))
    )
    (net (code "113") (name "unconnected-(IC33D-IO_L9P_MRCC_15-PadN28)") (class "Default")
      (node (ref "IC33") (pin "N28") (pinfunction "IO_L9P_MRCC_15_N28") (pintype "bidirectional"))
    )
    (net (code "114") (name "unconnected-(IC33D-IO_L10N_MRCC_15-PadM33)") (class "Default")
      (node (ref "IC33") (pin "M33") (pinfunction "IO_L10N_MRCC_15_M33") (pintype "bidirectional"))
    )
    (net (code "115") (name "unconnected-(IC33D-IO_L11N_SRCC_15-PadL30)") (class "Default")
      (node (ref "IC33") (pin "L30") (pinfunction "IO_L11N_SRCC_15_L30") (pintype "bidirectional"))
    )
    (net (code "116") (name "unconnected-(IC33D-IO_L11P_SRCC_15-PadL29)") (class "Default")
      (node (ref "IC33") (pin "L29") (pinfunction "IO_L11P_SRCC_15_L29") (pintype "bidirectional"))
    )
    (net (code "117") (name "unconnected-(IC33E-IO_L9N_MRCC_16-PadK27)") (class "Default")
      (node (ref "IC33") (pin "K27") (pinfunction "IO_L9N_MRCC_16_K27") (pintype "bidirectional"))
    )
    (net (code "118") (name "unconnected-(IC33E-IO_L9P_MRCC_16-PadK26)") (class "Default")
      (node (ref "IC33") (pin "K26") (pinfunction "IO_L9P_MRCC_16_K26") (pintype "bidirectional"))
    )
    (net (code "119") (name "unconnected-(IC33E-IO_L10N_MRCC_16-PadG33)") (class "Default")
      (node (ref "IC33") (pin "G33") (pinfunction "IO_L10N_MRCC_16_G33") (pintype "bidirectional"))
    )
    (net (code "120") (name "unconnected-(IC33E-IO_L10P_MRCC_16-PadF33)") (class "Default")
      (node (ref "IC33") (pin "F33") (pinfunction "IO_L10P_MRCC_16_F33") (pintype "bidirectional"))
    )
    (net (code "121") (name "unconnected-(IC33E-IO_L11N_SRCC_16-PadE31)") (class "Default")
      (node (ref "IC33") (pin "E31") (pinfunction "IO_L11N_SRCC_16_E31") (pintype "bidirectional"))
    )
    (net (code "122") (name "unconnected-(IC33E-IO_L11P_SRCC_16-PadF31)") (class "Default")
      (node (ref "IC33") (pin "F31") (pinfunction "IO_L11P_SRCC_16_F31") (pintype "bidirectional"))
    )
  )
)
